# pomodoro-py32f002b.net
KiCad netlist of a schematic drawn in EAGLE
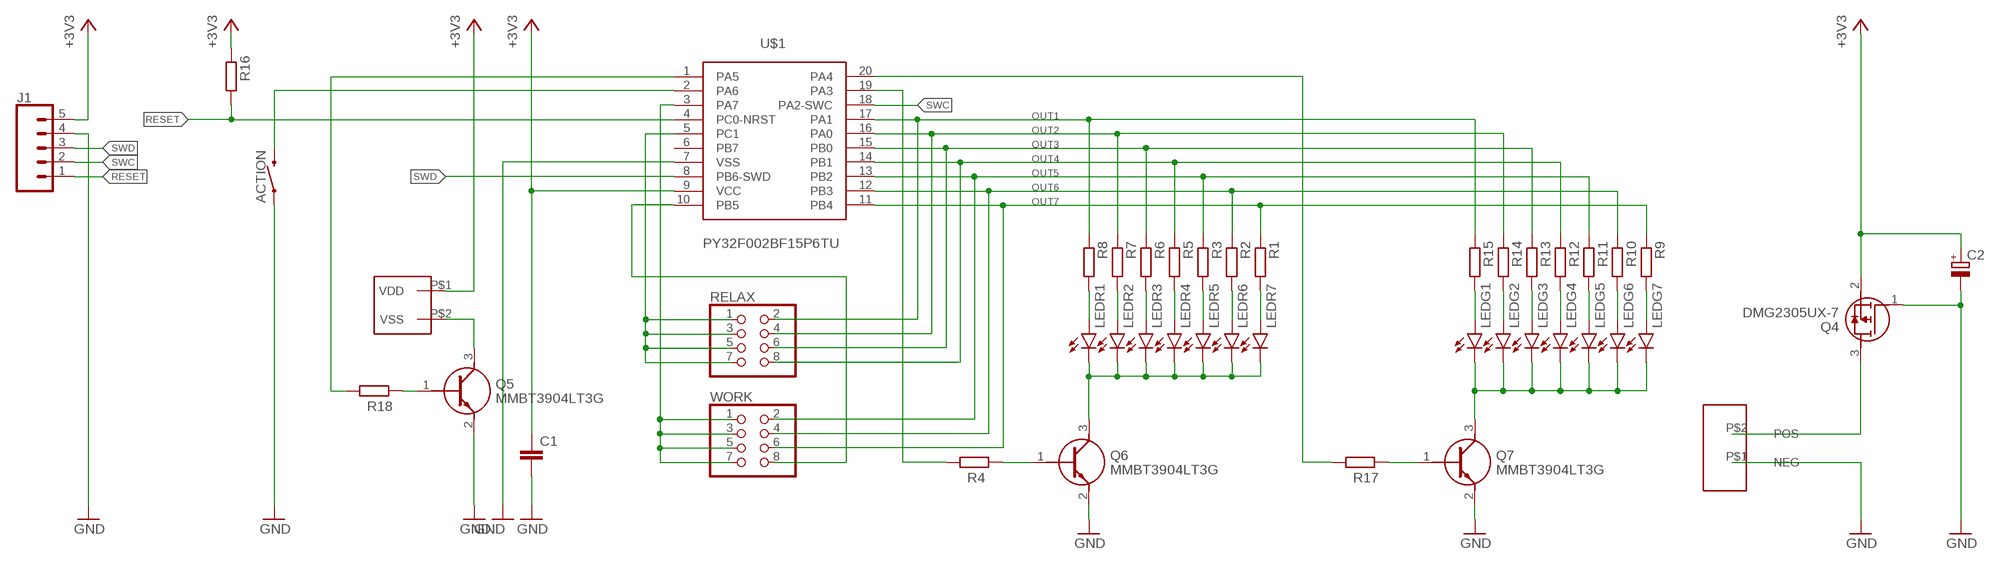
[diagram p0: schematic, sheet 1]

(export (version "E")
  (design (tool "Eeschema 10.0.6"))
  (components
    (comp (ref "ACTION")
      (value "MOMENTARY-SWITCH-SPST-SMD-6.0X3.5MM")
      (footprint "eagle-import:TACTILE_SWITCH_SMD_6.0X3.5MM")
      (libsource (lib "eagle-import") (part "MOMENTARY-SWITCH-SPST-SMD-6.0X3.5MM"))
    )
    (comp (ref "C1")
      (value "C-EUC0805")
      (footprint "eagle-import:C0805")
      (libsource (lib "eagle-import") (part "C-EUC0805"))
    )
    (comp (ref "C2")
      (value "CPOL-EUE2.5-5")
      (footprint "eagle-import:E2,5-5")
      (libsource (lib "eagle-import") (part "CPOL-EUE2.5-5"))
    )
    (comp (ref "J1")
      (value "CONN_05")
      (footprint "eagle-import:1X05")
      (libsource (lib "eagle-import") (part "CONN_05"))
    )
    (comp (ref "LEDG1")
      (value "20ma")
      (footprint "eagle-import:LED-0603")
      (libsource (lib "eagle-import") (part "LED0603"))
    )
    (comp (ref "LEDG2")
      (value "20ma")
      (footprint "eagle-import:LED-0603")
      (libsource (lib "eagle-import") (part "LED0603"))
    )
    (comp (ref "LEDG3")
      (value "20ma")
      (footprint "eagle-import:LED-0603")
      (libsource (lib "eagle-import") (part "LED0603"))
    )
    (comp (ref "LEDG4")
      (value "20ma")
      (footprint "eagle-import:LED-0603")
      (libsource (lib "eagle-import") (part "LED0603"))
    )
    (comp (ref "LEDG5")
      (value "20ma")
      (footprint "eagle-import:LED-0603")
      (libsource (lib "eagle-import") (part "LED0603"))
    )
    (comp (ref "LEDG6")
      (value "20ma")
      (footprint "eagle-import:LED-0603")
      (libsource (lib "eagle-import") (part "LED0603"))
    )
    (comp (ref "LEDG7")
      (value "20ma")
      (footprint "eagle-import:LED-0603")
      (libsource (lib "eagle-import") (part "LED0603"))
    )
    (comp (ref "LEDR1")
      (value "20ma")
      (footprint "eagle-import:LED-0603")
      (libsource (lib "eagle-import") (part "LED0603"))
    )
    (comp (ref "LEDR2")
      (value "20ma")
      (footprint "eagle-import:LED-0603")
      (libsource (lib "eagle-import") (part "LED0603"))
    )
    (comp (ref "LEDR3")
      (value "20ma")
      (footprint "eagle-import:LED-0603")
      (libsource (lib "eagle-import") (part "LED0603"))
    )
    (comp (ref "LEDR4")
      (value "20ma")
      (footprint "eagle-import:LED-0603")
      (libsource (lib "eagle-import") (part "LED0603"))
    )
    (comp (ref "LEDR5")
      (value "20ma")
      (footprint "eagle-import:LED-0603")
      (libsource (lib "eagle-import") (part "LED0603"))
    )
    (comp (ref "LEDR6")
      (value "20ma")
      (footprint "eagle-import:LED-0603")
      (libsource (lib "eagle-import") (part "LED0603"))
    )
    (comp (ref "LEDR7")
      (value "20ma")
      (footprint "eagle-import:LED-0603")
      (libsource (lib "eagle-import") (part "LED0603"))
    )
    (comp (ref "Q4")
      (value "DMG2305UX-7")
      (footprint "eagle-import:SOT96P240X115-3N")
      (fields (field (name "MOUSER_PART_NUMBER") "621-DMG2305UX-7"))
      (libsource (lib "eagle-import") (part "DMG2305UX-7"))
    )
    (comp (ref "Q5")
      (value "MMBT3904LT3G")
      (footprint "eagle-import:SOT96P237X111-3N")
      (fields (field (name "MOUSER_PART_NUMBER") "863-MMBT3904LT3G"))
      (libsource (lib "eagle-import") (part "MMBT3904LT3G"))
    )
    (comp (ref "Q6")
      (value "MMBT3904LT3G")
      (footprint "eagle-import:SOT96P237X111-3N")
      (fields (field (name "MOUSER_PART_NUMBER") "863-MMBT3904LT3G"))
      (libsource (lib "eagle-import") (part "MMBT3904LT3G"))
    )
    (comp (ref "Q7")
      (value "MMBT3904LT3G")
      (footprint "eagle-import:SOT96P237X111-3N")
      (fields (field (name "MOUSER_PART_NUMBER") "863-MMBT3904LT3G"))
      (libsource (lib "eagle-import") (part "MMBT3904LT3G"))
    )
    (comp (ref "R1")
      (value "100R")
      (footprint "eagle-import:R0805")
      (libsource (lib "eagle-import") (part "R-EU_R0805"))
    )
    (comp (ref "R2")
      (value "100R")
      (footprint "eagle-import:R0805")
      (libsource (lib "eagle-import") (part "R-EU_R0805"))
    )
    (comp (ref "R3")
      (value "100R")
      (footprint "eagle-import:R0805")
      (libsource (lib "eagle-import") (part "R-EU_R0805"))
    )
    (comp (ref "R4")
      (value "10k")
      (footprint "eagle-import:R0805")
      (libsource (lib "eagle-import") (part "R-EU_R0805"))
    )
    (comp (ref "R5")
      (value "100R")
      (footprint "eagle-import:R0805")
      (libsource (lib "eagle-import") (part "R-EU_R0805"))
    )
    (comp (ref "R6")
      (value "100R")
      (footprint "eagle-import:R0805")
      (libsource (lib "eagle-import") (part "R-EU_R0805"))
    )
    (comp (ref "R7")
      (value "100R")
      (footprint "eagle-import:R0805")
      (libsource (lib "eagle-import") (part "R-EU_R0805"))
    )
    (comp (ref "R8")
      (value "100R")
      (footprint "eagle-import:R0805")
      (libsource (lib "eagle-import") (part "R-EU_R0805"))
    )
    (comp (ref "R9")
      (value "100R")
      (footprint "eagle-import:R0805")
      (libsource (lib "eagle-import") (part "R-EU_R0805"))
    )
    (comp (ref "R10")
      (value "100R")
      (footprint "eagle-import:R0805")
      (libsource (lib "eagle-import") (part "R-EU_R0805"))
    )
    (comp (ref "R11")
      (value "100R")
      (footprint "eagle-import:R0805")
      (libsource (lib "eagle-import") (part "R-EU_R0805"))
    )
    (comp (ref "R12")
      (value "100R")
      (footprint "eagle-import:R0805")
      (libsource (lib "eagle-import") (part "R-EU_R0805"))
    )
    (comp (ref "R13")
      (value "100R")
      (footprint "eagle-import:R0805")
      (libsource (lib "eagle-import") (part "R-EU_R0805"))
    )
    (comp (ref "R14")
      (value "100R")
      (footprint "eagle-import:R0805")
      (libsource (lib "eagle-import") (part "R-EU_R0805"))
    )
    (comp (ref "R15")
      (value "100R")
      (footprint "eagle-import:R0805")
      (libsource (lib "eagle-import") (part "R-EU_R0805"))
    )
    (comp (ref "R16")
      (value "100R")
      (footprint "eagle-import:R0805")
      (libsource (lib "eagle-import") (part "R-EU_R0805"))
    )
    (comp (ref "R17")
      (value "10K")
      (footprint "eagle-import:R0805")
      (libsource (lib "eagle-import") (part "R-EU_R0805"))
    )
    (comp (ref "R18")
      (value "10k")
      (footprint "eagle-import:R0805")
      (libsource (lib "eagle-import") (part "R-EU_R0805"))
    )
    (comp (ref "RELAX")
      (value "PINHD-2X4")
      (footprint "eagle-import:2X04")
      (libsource (lib "eagle-import") (part "PINHD-2X4"))
    )
    (comp (ref "U$1")
      (value "PY32F002BF15P6TU")
      (footprint "eagle-import:TSSOP20")
      (libsource (lib "eagle-import") (part "PY32F002BF15P6TU"))
    )
    (comp (ref "U$2")
      (value "BUZZER8X8")
      (footprint "eagle-import:BUZZER8X8")
      (libsource (lib "eagle-import") (part "BUZZER8X8"))
    )
    (comp (ref "U$3")
      (value "2AAABATT")
      (footprint "eagle-import:2AAABATTSER")
      (libsource (lib "eagle-import") (part "2AAABATT"))
    )
    (comp (ref "WORK")
      (value "PINHD-2X4")
      (footprint "eagle-import:2X04")
      (libsource (lib "eagle-import") (part "PINHD-2X4"))
    )
  )
  (nets
    (net (code "1") (name "+3V3") (class "Default")
      (node (ref "C1") (pin "1") (pinfunction "1_1") (pintype "passive"))
      (node (ref "C2") (pin "+") (pinfunction "+_+") (pintype "passive"))
      (node (ref "J1") (pin "5") (pinfunction "5_5") (pintype "passive"))
      (node (ref "Q4") (pin "2") (pinfunction "S_2") (pintype "bidirectional"))
      (node (ref "R16") (pin "1") (pinfunction "1_1") (pintype "passive"))
      (node (ref "U$1") (pin "9") (pinfunction "VCC_9") (pintype "bidirectional"))
      (node (ref "U$2") (pin "P$1") (pinfunction "VDD_P$1") (pintype "bidirectional"))
    )
    (net (code "2") (name "/OUT1") (class "Default")
      (node (ref "R15") (pin "1") (pinfunction "1_1") (pintype "passive"))
      (node (ref "R8") (pin "1") (pinfunction "1_1") (pintype "passive"))
      (node (ref "RELAX") (pin "2") (pinfunction "2_2") (pintype "passive"))
      (node (ref "U$1") (pin "17") (pinfunction "PA1_17") (pintype "bidirectional"))
    )
    (net (code "3") (name "/OUT2") (class "Default")
      (node (ref "R14") (pin "1") (pinfunction "1_1") (pintype "passive"))
      (node (ref "R7") (pin "1") (pinfunction "1_1") (pintype "passive"))
      (node (ref "RELAX") (pin "4") (pinfunction "4_4") (pintype "passive"))
      (node (ref "U$1") (pin "16") (pinfunction "PA0_16") (pintype "bidirectional"))
    )
    (net (code "4") (name "/OUT3") (class "Default")
      (node (ref "R13") (pin "1") (pinfunction "1_1") (pintype "passive"))
      (node (ref "R6") (pin "1") (pinfunction "1_1") (pintype "passive"))
      (node (ref "RELAX") (pin "6") (pinfunction "6_6") (pintype "passive"))
      (node (ref "U$1") (pin "15") (pinfunction "PB0_15") (pintype "bidirectional"))
    )
    (net (code "5") (name "/OUT4") (class "Default")
      (node (ref "R12") (pin "1") (pinfunction "1_1") (pintype "passive"))
      (node (ref "R5") (pin "1") (pinfunction "1_1") (pintype "passive"))
      (node (ref "RELAX") (pin "8") (pinfunction "8_8") (pintype "passive"))
      (node (ref "U$1") (pin "14") (pinfunction "PB1_14") (pintype "bidirectional"))
    )
    (net (code "6") (name "/OUT5") (class "Default")
      (node (ref "R11") (pin "1") (pinfunction "1_1") (pintype "passive"))
      (node (ref "R3") (pin "1") (pinfunction "1_1") (pintype "passive"))
      (node (ref "U$1") (pin "13") (pinfunction "PB2_13") (pintype "bidirectional"))
      (node (ref "WORK") (pin "2") (pinfunction "2_2") (pintype "passive"))
    )
    (net (code "7") (name "/OUT6") (class "Default")
      (node (ref "R10") (pin "1") (pinfunction "1_1") (pintype "passive"))
      (node (ref "R2") (pin "1") (pinfunction "1_1") (pintype "passive"))
      (node (ref "U$1") (pin "12") (pinfunction "PB3_12") (pintype "bidirectional"))
      (node (ref "WORK") (pin "4") (pinfunction "4_4") (pintype "passive"))
    )
    (net (code "8") (name "/OUT7") (class "Default")
      (node (ref "R1") (pin "1") (pinfunction "1_1") (pintype "passive"))
      (node (ref "R9") (pin "1") (pinfunction "1_1") (pintype "passive"))
      (node (ref "U$1") (pin "11") (pinfunction "PB4_11") (pintype "bidirectional"))
      (node (ref "WORK") (pin "6") (pinfunction "6_6") (pintype "passive"))
    )
    (net (code "9") (name "GND") (class "Default")
      (node (ref "ACTION") (pin "1") (pinfunction "1_1") (pintype "passive"))
      (node (ref "C1") (pin "2") (pinfunction "2_2") (pintype "passive"))
      (node (ref "C2") (pin "-") (pinfunction "-_-") (pintype "passive"))
      (node (ref "J1") (pin "4") (pinfunction "4_4") (pintype "passive"))
      (node (ref "Q4") (pin "1") (pinfunction "G_1") (pintype "bidirectional"))
      (node (ref "Q5") (pin "2") (pinfunction "E_2") (pintype "bidirectional"))
      (node (ref "Q6") (pin "2") (pinfunction "E_2") (pintype "bidirectional"))
      (node (ref "Q7") (pin "2") (pinfunction "E_2") (pintype "bidirectional"))
      (node (ref "U$1") (pin "7") (pinfunction "VSS_7") (pintype "bidirectional"))
      (node (ref "U$3") (pin "P$1") (pinfunction "NEG_P$1") (pintype "power_in"))
    )
    (net (code "10") (name "Net-(LEDG1-PadA)") (class "Default")
      (node (ref "LEDG1") (pin "A") (pinfunction "A_A") (pintype "passive"))
      (node (ref "R15") (pin "2") (pinfunction "2_2") (pintype "passive"))
    )
    (net (code "11") (name "Net-(LEDG2-PadA)") (class "Default")
      (node (ref "LEDG2") (pin "A") (pinfunction "A_A") (pintype "passive"))
      (node (ref "R14") (pin "2") (pinfunction "2_2") (pintype "passive"))
    )
    (net (code "12") (name "Net-(LEDG3-PadA)") (class "Default")
      (node (ref "LEDG3") (pin "A") (pinfunction "A_A") (pintype "passive"))
      (node (ref "R13") (pin "2") (pinfunction "2_2") (pintype "passive"))
    )
    (net (code "13") (name "Net-(LEDG4-PadA)") (class "Default")
      (node (ref "LEDG4") (pin "A") (pinfunction "A_A") (pintype "passive"))
      (node (ref "R12") (pin "2") (pinfunction "2_2") (pintype "passive"))
    )
    (net (code "14") (name "Net-(LEDG5-PadA)") (class "Default")
      (node (ref "LEDG5") (pin "A") (pinfunction "A_A") (pintype "passive"))
      (node (ref "R11") (pin "2") (pinfunction "2_2") (pintype "passive"))
    )
    (net (code "15") (name "Net-(LEDG6-PadA)") (class "Default")
      (node (ref "LEDG6") (pin "A") (pinfunction "A_A") (pintype "passive"))
      (node (ref "R10") (pin "2") (pinfunction "2_2") (pintype "passive"))
    )
    (net (code "16") (name "Net-(LEDG7-PadA)") (class "Default")
      (node (ref "LEDG7") (pin "A") (pinfunction "A_A") (pintype "passive"))
      (node (ref "R9") (pin "2") (pinfunction "2_2") (pintype "passive"))
    )
    (net (code "17") (name "Net-(LEDR1-PadA)") (class "Default")
      (node (ref "LEDR1") (pin "A") (pinfunction "A_A") (pintype "passive"))
      (node (ref "R8") (pin "2") (pinfunction "2_2") (pintype "passive"))
    )
    (net (code "18") (name "Net-(LEDR2-PadA)") (class "Default")
      (node (ref "LEDR2") (pin "A") (pinfunction "A_A") (pintype "passive"))
      (node (ref "R7") (pin "2") (pinfunction "2_2") (pintype "passive"))
    )
    (net (code "19") (name "Net-(LEDR3-PadA)") (class "Default")
      (node (ref "LEDR3") (pin "A") (pinfunction "A_A") (pintype "passive"))
      (node (ref "R6") (pin "2") (pinfunction "2_2") (pintype "passive"))
    )
    (net (code "20") (name "Net-(LEDR4-PadA)") (class "Default")
      (node (ref "LEDR4") (pin "A") (pinfunction "A_A") (pintype "passive"))
      (node (ref "R5") (pin "2") (pinfunction "2_2") (pintype "passive"))
    )
    (net (code "21") (name "Net-(LEDR5-PadA)") (class "Default")
      (node (ref "LEDR5") (pin "A") (pinfunction "A_A") (pintype "passive"))
      (node (ref "R3") (pin "2") (pinfunction "2_2") (pintype "passive"))
    )
    (net (code "22") (name "Net-(LEDR6-PadA)") (class "Default")
      (node (ref "LEDR6") (pin "A") (pinfunction "A_A") (pintype "passive"))
      (node (ref "R2") (pin "2") (pinfunction "2_2") (pintype "passive"))
    )
    (net (code "23") (name "Net-(LEDR7-PadA)") (class "Default")
      (node (ref "LEDR7") (pin "A") (pinfunction "A_A") (pintype "passive"))
      (node (ref "R1") (pin "2") (pinfunction "2_2") (pintype "passive"))
    )
    (net (code "24") (name "Net-(Q4-D)") (class "Default")
      (node (ref "Q4") (pin "3") (pinfunction "D_3") (pintype "bidirectional"))
      (node (ref "U$3") (pin "P$2") (pinfunction "POS_P$2") (pintype "power_in"))
    )
    (net (code "25") (name "Net-(Q5-B)") (class "Default")
      (node (ref "Q5") (pin "1") (pinfunction "B_1") (pintype "bidirectional"))
      (node (ref "R18") (pin "2") (pinfunction "2_2") (pintype "passive"))
    )
    (net (code "26") (name "Net-(Q5-C)") (class "Default")
      (node (ref "Q5") (pin "3") (pinfunction "C_3") (pintype "bidirectional"))
      (node (ref "U$2") (pin "P$2") (pinfunction "VSS_P$2") (pintype "bidirectional"))
    )
    (net (code "27") (name "Net-(Q6-B)") (class "Default")
      (node (ref "Q6") (pin "1") (pinfunction "B_1") (pintype "bidirectional"))
      (node (ref "R4") (pin "2") (pinfunction "2_2") (pintype "passive"))
    )
    (net (code "28") (name "Net-(Q6-C)") (class "Default")
      (node (ref "LEDR1") (pin "C") (pinfunction "C_C") (pintype "passive"))
      (node (ref "LEDR2") (pin "C") (pinfunction "C_C") (pintype "passive"))
      (node (ref "LEDR3") (pin "C") (pinfunction "C_C") (pintype "passive"))
      (node (ref "LEDR4") (pin "C") (pinfunction "C_C") (pintype "passive"))
      (node (ref "LEDR5") (pin "C") (pinfunction "C_C") (pintype "passive"))
      (node (ref "LEDR6") (pin "C") (pinfunction "C_C") (pintype "passive"))
      (node (ref "LEDR7") (pin "C") (pinfunction "C_C") (pintype "passive"))
      (node (ref "Q6") (pin "3") (pinfunction "C_3") (pintype "bidirectional"))
    )
    (net (code "29") (name "Net-(Q7-B)") (class "Default")
      (node (ref "Q7") (pin "1") (pinfunction "B_1") (pintype "bidirectional"))
      (node (ref "R17") (pin "2") (pinfunction "2_2") (pintype "passive"))
    )
    (net (code "30") (name "Net-(Q7-C)") (class "Default")
      (node (ref "LEDG1") (pin "C") (pinfunction "C_C") (pintype "passive"))
      (node (ref "LEDG2") (pin "C") (pinfunction "C_C") (pintype "passive"))
      (node (ref "LEDG3") (pin "C") (pinfunction "C_C") (pintype "passive"))
      (node (ref "LEDG4") (pin "C") (pinfunction "C_C") (pintype "passive"))
      (node (ref "LEDG5") (pin "C") (pinfunction "C_C") (pintype "passive"))
      (node (ref "LEDG6") (pin "C") (pinfunction "C_C") (pintype "passive"))
      (node (ref "LEDG7") (pin "C") (pinfunction "C_C") (pintype "passive"))
      (node (ref "Q7") (pin "3") (pinfunction "C_3") (pintype "bidirectional"))
    )
    (net (code "31") (name "Net-(U$1-PA3)") (class "Default")
      (node (ref "R4") (pin "1") (pinfunction "1_1") (pintype "passive"))
      (node (ref "U$1") (pin "19") (pinfunction "PA3_19") (pintype "bidirectional"))
    )
    (net (code "32") (name "Net-(U$1-PA4)") (class "Default")
      (node (ref "R17") (pin "1") (pinfunction "1_1") (pintype "passive"))
      (node (ref "U$1") (pin "20") (pinfunction "PA4_20") (pintype "bidirectional"))
    )
    (net (code "33") (name "Net-(U$1-PA5)") (class "Default")
      (node (ref "R18") (pin "1") (pinfunction "1_1") (pintype "passive"))
      (node (ref "U$1") (pin "1") (pinfunction "PA5_1") (pintype "bidirectional"))
    )
    (net (code "34") (name "Net-(U$1-PA6)") (class "Default")
      (node (ref "ACTION") (pin "2") (pinfunction "2_2") (pintype "passive"))
      (node (ref "U$1") (pin "2") (pinfunction "PA6_2") (pintype "bidirectional"))
    )
    (net (code "35") (name "Net-(U$1-PA7)") (class "Default")
      (node (ref "U$1") (pin "3") (pinfunction "PA7_3") (pintype "bidirectional"))
      (node (ref "WORK") (pin "1") (pinfunction "1_1") (pintype "passive"))
      (node (ref "WORK") (pin "3") (pinfunction "3_3") (pintype "passive"))
      (node (ref "WORK") (pin "5") (pinfunction "5_5") (pintype "passive"))
      (node (ref "WORK") (pin "7") (pinfunction "7_7") (pintype "passive"))
    )
    (net (code "36") (name "Net-(U$1-PB5)") (class "Default")
      (node (ref "U$1") (pin "10") (pinfunction "PB5_10") (pintype "bidirectional"))
      (node (ref "WORK") (pin "8") (pinfunction "8_8") (pintype "passive"))
    )
    (net (code "37") (name "Net-(U$1-PC1)") (class "Default")
      (node (ref "RELAX") (pin "1") (pinfunction "1_1") (pintype "passive"))
      (node (ref "RELAX") (pin "3") (pinfunction "3_3") (pintype "passive"))
      (node (ref "RELAX") (pin "5") (pinfunction "5_5") (pintype "passive"))
      (node (ref "RELAX") (pin "7") (pinfunction "7_7") (pintype "passive"))
      (node (ref "U$1") (pin "5") (pinfunction "PC1_5") (pintype "bidirectional"))
    )
    (net (code "38") (name "RESET") (class "Default")
      (node (ref "J1") (pin "1") (pinfunction "1_1") (pintype "passive"))
      (node (ref "R16") (pin "2") (pinfunction "2_2") (pintype "passive"))
      (node (ref "U$1") (pin "4") (pinfunction "PC0-NRST_4") (pintype "bidirectional"))
    )
    (net (code "39") (name "SWC") (class "Default")
      (node (ref "J1") (pin "2") (pinfunction "2_2") (pintype "passive"))
      (node (ref "U$1") (pin "18") (pinfunction "PA2-SWC_18") (pintype "bidirectional"))
    )
    (net (code "40") (name "SWD") (class "Default")
      (node (ref "J1") (pin "3") (pinfunction "3_3") (pintype "passive"))
      (node (ref "U$1") (pin "8") (pinfunction "PB6-SWD_8") (pintype "bidirectional"))
    )
    (net (code "41") (name "unconnected-(U$1-PB7-Pad6)") (class "Default")
      (node (ref "U$1") (pin "6") (pinfunction "PB7_6") (pintype "bidirectional"))
    )
  )
)
